# LED_Array.net
KiCad netlist of a schematic drawn in Altium Designer
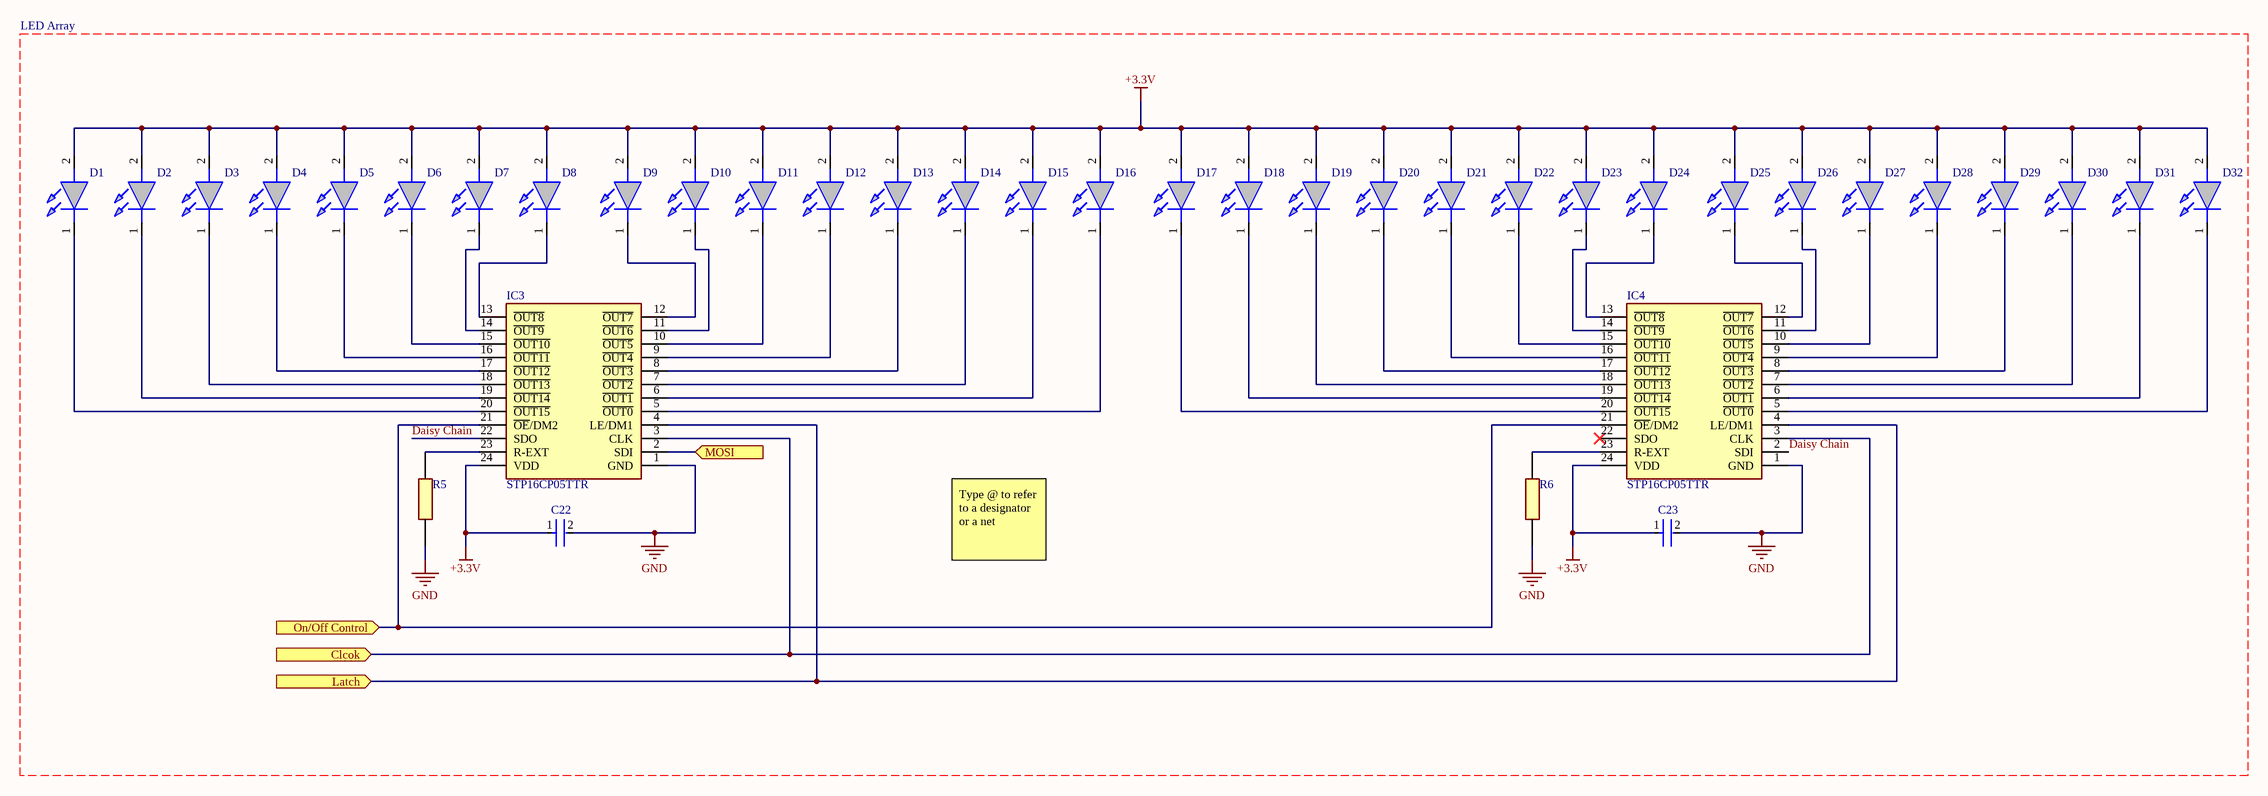
[diagram p0: LED_Array.SchDoc]

(export (version "E")
  (design (tool "Eeschema 10.0.6"))
  (components
    (comp (ref "C22")
      (value "CL31B104KBP5PNF")
      (footprint "FP-CL31-IPC_C")
      (description "Cap Ceramic 100nF 50V X7R ±10% SMD 1206 +125°C Embossed T/R")
      (fields (field (name "TOLERANCE") "10%"))
      (libsource (lib "Altium Content Vault") (part "b4654b650e69147ec39a6b967a45e02"))
    )
    (comp (ref "C23")
      (value "CL31B104KBP5PNF")
      (footprint "FP-CL31-IPC_C")
      (description "Cap Ceramic 100nF 50V X7R ±10% SMD 1206 +125°C Embossed T/R")
      (fields (field (name "TOLERANCE") "10%"))
      (libsource (lib "Altium Content Vault") (part "b4654b650e69147ec39a6b967a45e02"))
    )
    (comp (ref "D1")
      (value "LR_T64F-BBDB-1-1")
      (footprint "LEDM3528X380N")
      (description "Standard LEDs - SMD Red")
      (fields
        (field (name "MOUSER PART NUMBER") "720-LRT64FBBDB11")
        (field (name "MANUFACTURER_PART_NUMBER") "LR T64F-BBDB-1-1")
      )
      (libsource (lib "LR_T64F-BBDB-1-1") (part "LR_T64F-BBDB-1-1"))
    )
    (comp (ref "D2")
      (value "LR_T64F-BBDB-1-1")
      (footprint "LEDM3528X380N")
      (description "Standard LEDs - SMD Red")
      (fields
        (field (name "MOUSER PART NUMBER") "720-LRT64FBBDB11")
        (field (name "MANUFACTURER_PART_NUMBER") "LR T64F-BBDB-1-1")
      )
      (libsource (lib "LR_T64F-BBDB-1-1") (part "LR_T64F-BBDB-1-1"))
    )
    (comp (ref "D3")
      (value "LR_T64F-BBDB-1-1")
      (footprint "LEDM3528X380N")
      (description "Standard LEDs - SMD Red")
      (fields
        (field (name "MOUSER PART NUMBER") "720-LRT64FBBDB11")
        (field (name "MANUFACTURER_PART_NUMBER") "LR T64F-BBDB-1-1")
      )
      (libsource (lib "LR_T64F-BBDB-1-1") (part "LR_T64F-BBDB-1-1"))
    )
    (comp (ref "D4")
      (value "LR_T64F-BBDB-1-1")
      (footprint "LEDM3528X380N")
      (description "Standard LEDs - SMD Red")
      (fields
        (field (name "MOUSER PART NUMBER") "720-LRT64FBBDB11")
        (field (name "MANUFACTURER_PART_NUMBER") "LR T64F-BBDB-1-1")
      )
      (libsource (lib "LR_T64F-BBDB-1-1") (part "LR_T64F-BBDB-1-1"))
    )
    (comp (ref "D5")
      (value "LR_T64F-BBDB-1-1")
      (footprint "LEDM3528X380N")
      (description "Standard LEDs - SMD Red")
      (fields
        (field (name "MOUSER PART NUMBER") "720-LRT64FBBDB11")
        (field (name "MANUFACTURER_PART_NUMBER") "LR T64F-BBDB-1-1")
      )
      (libsource (lib "LR_T64F-BBDB-1-1") (part "LR_T64F-BBDB-1-1"))
    )
    (comp (ref "D6")
      (value "LR_T64F-BBDB-1-1")
      (footprint "LEDM3528X380N")
      (description "Standard LEDs - SMD Red")
      (fields
        (field (name "MOUSER PART NUMBER") "720-LRT64FBBDB11")
        (field (name "MANUFACTURER_PART_NUMBER") "LR T64F-BBDB-1-1")
      )
      (libsource (lib "LR_T64F-BBDB-1-1") (part "LR_T64F-BBDB-1-1"))
    )
    (comp (ref "D7")
      (value "LR_T64F-BBDB-1-1")
      (footprint "LEDM3528X380N")
      (description "Standard LEDs - SMD Red")
      (fields
        (field (name "MOUSER PART NUMBER") "720-LRT64FBBDB11")
        (field (name "MANUFACTURER_PART_NUMBER") "LR T64F-BBDB-1-1")
      )
      (libsource (lib "LR_T64F-BBDB-1-1") (part "LR_T64F-BBDB-1-1"))
    )
    (comp (ref "D8")
      (value "LR_T64F-BBDB-1-1")
      (footprint "LEDM3528X380N")
      (description "Standard LEDs - SMD Red")
      (fields
        (field (name "MOUSER PART NUMBER") "720-LRT64FBBDB11")
        (field (name "MANUFACTURER_PART_NUMBER") "LR T64F-BBDB-1-1")
      )
      (libsource (lib "LR_T64F-BBDB-1-1") (part "LR_T64F-BBDB-1-1"))
    )
    (comp (ref "D9")
      (value "LR_T64F-BBDB-1-1")
      (footprint "LEDM3528X380N")
      (description "Standard LEDs - SMD Red")
      (fields
        (field (name "MOUSER PART NUMBER") "720-LRT64FBBDB11")
        (field (name "MANUFACTURER_PART_NUMBER") "LR T64F-BBDB-1-1")
      )
      (libsource (lib "LR_T64F-BBDB-1-1") (part "LR_T64F-BBDB-1-1"))
    )
    (comp (ref "D10")
      (value "LR_T64F-BBDB-1-1")
      (footprint "LEDM3528X380N")
      (description "Standard LEDs - SMD Red")
      (fields
        (field (name "MOUSER PART NUMBER") "720-LRT64FBBDB11")
        (field (name "MANUFACTURER_PART_NUMBER") "LR T64F-BBDB-1-1")
      )
      (libsource (lib "LR_T64F-BBDB-1-1") (part "LR_T64F-BBDB-1-1"))
    )
    (comp (ref "D11")
      (value "LR_T64F-BBDB-1-1")
      (footprint "LEDM3528X380N")
      (description "Standard LEDs - SMD Red")
      (fields
        (field (name "MOUSER PART NUMBER") "720-LRT64FBBDB11")
        (field (name "MANUFACTURER_PART_NUMBER") "LR T64F-BBDB-1-1")
      )
      (libsource (lib "LR_T64F-BBDB-1-1") (part "LR_T64F-BBDB-1-1"))
    )
    (comp (ref "D12")
      (value "LR_T64F-BBDB-1-1")
      (footprint "LEDM3528X380N")
      (description "Standard LEDs - SMD Red")
      (fields
        (field (name "MOUSER PART NUMBER") "720-LRT64FBBDB11")
        (field (name "MANUFACTURER_PART_NUMBER") "LR T64F-BBDB-1-1")
      )
      (libsource (lib "LR_T64F-BBDB-1-1") (part "LR_T64F-BBDB-1-1"))
    )
    (comp (ref "D13")
      (value "LR_T64F-BBDB-1-1")
      (footprint "LEDM3528X380N")
      (description "Standard LEDs - SMD Red")
      (fields
        (field (name "MOUSER PART NUMBER") "720-LRT64FBBDB11")
        (field (name "MANUFACTURER_PART_NUMBER") "LR T64F-BBDB-1-1")
      )
      (libsource (lib "LR_T64F-BBDB-1-1") (part "LR_T64F-BBDB-1-1"))
    )
    (comp (ref "D14")
      (value "LR_T64F-BBDB-1-1")
      (footprint "LEDM3528X380N")
      (description "Standard LEDs - SMD Red")
      (fields
        (field (name "MOUSER PART NUMBER") "720-LRT64FBBDB11")
        (field (name "MANUFACTURER_PART_NUMBER") "LR T64F-BBDB-1-1")
      )
      (libsource (lib "LR_T64F-BBDB-1-1") (part "LR_T64F-BBDB-1-1"))
    )
    (comp (ref "D15")
      (value "LR_T64F-BBDB-1-1")
      (footprint "LEDM3528X380N")
      (description "Standard LEDs - SMD Red")
      (fields
        (field (name "MOUSER PART NUMBER") "720-LRT64FBBDB11")
        (field (name "MANUFACTURER_PART_NUMBER") "LR T64F-BBDB-1-1")
      )
      (libsource (lib "LR_T64F-BBDB-1-1") (part "LR_T64F-BBDB-1-1"))
    )
    (comp (ref "D16")
      (value "LR_T64F-BBDB-1-1")
      (footprint "LEDM3528X380N")
      (description "Standard LEDs - SMD Red")
      (fields
        (field (name "MOUSER PART NUMBER") "720-LRT64FBBDB11")
        (field (name "MANUFACTURER_PART_NUMBER") "LR T64F-BBDB-1-1")
      )
      (libsource (lib "LR_T64F-BBDB-1-1") (part "LR_T64F-BBDB-1-1"))
    )
    (comp (ref "D17")
      (value "LR_T64F-BBDB-1-1")
      (footprint "LEDM3528X380N")
      (description "Standard LEDs - SMD Red")
      (fields
        (field (name "MOUSER PART NUMBER") "720-LRT64FBBDB11")
        (field (name "MANUFACTURER_PART_NUMBER") "LR T64F-BBDB-1-1")
      )
      (libsource (lib "LR_T64F-BBDB-1-1") (part "LR_T64F-BBDB-1-1"))
    )
    (comp (ref "D18")
      (value "LR_T64F-BBDB-1-1")
      (footprint "LEDM3528X380N")
      (description "Standard LEDs - SMD Red")
      (fields
        (field (name "MOUSER PART NUMBER") "720-LRT64FBBDB11")
        (field (name "MANUFACTURER_PART_NUMBER") "LR T64F-BBDB-1-1")
      )
      (libsource (lib "LR_T64F-BBDB-1-1") (part "LR_T64F-BBDB-1-1"))
    )
    (comp (ref "D19")
      (value "LR_T64F-BBDB-1-1")
      (footprint "LEDM3528X380N")
      (description "Standard LEDs - SMD Red")
      (fields
        (field (name "MOUSER PART NUMBER") "720-LRT64FBBDB11")
        (field (name "MANUFACTURER_PART_NUMBER") "LR T64F-BBDB-1-1")
      )
      (libsource (lib "LR_T64F-BBDB-1-1") (part "LR_T64F-BBDB-1-1"))
    )
    (comp (ref "D20")
      (value "LR_T64F-BBDB-1-1")
      (footprint "LEDM3528X380N")
      (description "Standard LEDs - SMD Red")
      (fields
        (field (name "MOUSER PART NUMBER") "720-LRT64FBBDB11")
        (field (name "MANUFACTURER_PART_NUMBER") "LR T64F-BBDB-1-1")
      )
      (libsource (lib "LR_T64F-BBDB-1-1") (part "LR_T64F-BBDB-1-1"))
    )
    (comp (ref "D21")
      (value "LR_T64F-BBDB-1-1")
      (footprint "LEDM3528X380N")
      (description "Standard LEDs - SMD Red")
      (fields
        (field (name "MOUSER PART NUMBER") "720-LRT64FBBDB11")
        (field (name "MANUFACTURER_PART_NUMBER") "LR T64F-BBDB-1-1")
      )
      (libsource (lib "LR_T64F-BBDB-1-1") (part "LR_T64F-BBDB-1-1"))
    )
    (comp (ref "D22")
      (value "LR_T64F-BBDB-1-1")
      (footprint "LEDM3528X380N")
      (description "Standard LEDs - SMD Red")
      (fields
        (field (name "MOUSER PART NUMBER") "720-LRT64FBBDB11")
        (field (name "MANUFACTURER_PART_NUMBER") "LR T64F-BBDB-1-1")
      )
      (libsource (lib "LR_T64F-BBDB-1-1") (part "LR_T64F-BBDB-1-1"))
    )
    (comp (ref "D23")
      (value "LR_T64F-BBDB-1-1")
      (footprint "LEDM3528X380N")
      (description "Standard LEDs - SMD Red")
      (fields
        (field (name "MOUSER PART NUMBER") "720-LRT64FBBDB11")
        (field (name "MANUFACTURER_PART_NUMBER") "LR T64F-BBDB-1-1")
      )
      (libsource (lib "LR_T64F-BBDB-1-1") (part "LR_T64F-BBDB-1-1"))
    )
    (comp (ref "D24")
      (value "LR_T64F-BBDB-1-1")
      (footprint "LEDM3528X380N")
      (description "Standard LEDs - SMD Red")
      (fields
        (field (name "MOUSER PART NUMBER") "720-LRT64FBBDB11")
        (field (name "MANUFACTURER_PART_NUMBER") "LR T64F-BBDB-1-1")
      )
      (libsource (lib "LR_T64F-BBDB-1-1") (part "LR_T64F-BBDB-1-1"))
    )
    (comp (ref "D25")
      (value "LR_T64F-BBDB-1-1")
      (footprint "LEDM3528X380N")
      (description "Standard LEDs - SMD Red")
      (fields
        (field (name "MOUSER PART NUMBER") "720-LRT64FBBDB11")
        (field (name "MANUFACTURER_PART_NUMBER") "LR T64F-BBDB-1-1")
      )
      (libsource (lib "LR_T64F-BBDB-1-1") (part "LR_T64F-BBDB-1-1"))
    )
    (comp (ref "D26")
      (value "LR_T64F-BBDB-1-1")
      (footprint "LEDM3528X380N")
      (description "Standard LEDs - SMD Red")
      (fields
        (field (name "MOUSER PART NUMBER") "720-LRT64FBBDB11")
        (field (name "MANUFACTURER_PART_NUMBER") "LR T64F-BBDB-1-1")
      )
      (libsource (lib "LR_T64F-BBDB-1-1") (part "LR_T64F-BBDB-1-1"))
    )
    (comp (ref "D27")
      (value "LR_T64F-BBDB-1-1")
      (footprint "LEDM3528X380N")
      (description "Standard LEDs - SMD Red")
      (fields
        (field (name "MOUSER PART NUMBER") "720-LRT64FBBDB11")
        (field (name "MANUFACTURER_PART_NUMBER") "LR T64F-BBDB-1-1")
      )
      (libsource (lib "LR_T64F-BBDB-1-1") (part "LR_T64F-BBDB-1-1"))
    )
    (comp (ref "D28")
      (value "LR_T64F-BBDB-1-1")
      (footprint "LEDM3528X380N")
      (description "Standard LEDs - SMD Red")
      (fields
        (field (name "MOUSER PART NUMBER") "720-LRT64FBBDB11")
        (field (name "MANUFACTURER_PART_NUMBER") "LR T64F-BBDB-1-1")
      )
      (libsource (lib "LR_T64F-BBDB-1-1") (part "LR_T64F-BBDB-1-1"))
    )
    (comp (ref "D29")
      (value "LR_T64F-BBDB-1-1")
      (footprint "LEDM3528X380N")
      (description "Standard LEDs - SMD Red")
      (fields
        (field (name "MOUSER PART NUMBER") "720-LRT64FBBDB11")
        (field (name "MANUFACTURER_PART_NUMBER") "LR T64F-BBDB-1-1")
      )
      (libsource (lib "LR_T64F-BBDB-1-1") (part "LR_T64F-BBDB-1-1"))
    )
    (comp (ref "D30")
      (value "LR_T64F-BBDB-1-1")
      (footprint "LEDM3528X380N")
      (description "Standard LEDs - SMD Red")
      (fields
        (field (name "MOUSER PART NUMBER") "720-LRT64FBBDB11")
        (field (name "MANUFACTURER_PART_NUMBER") "LR T64F-BBDB-1-1")
      )
      (libsource (lib "LR_T64F-BBDB-1-1") (part "LR_T64F-BBDB-1-1"))
    )
    (comp (ref "D31")
      (value "LR_T64F-BBDB-1-1")
      (footprint "LEDM3528X380N")
      (description "Standard LEDs - SMD Red")
      (fields
        (field (name "MOUSER PART NUMBER") "720-LRT64FBBDB11")
        (field (name "MANUFACTURER_PART_NUMBER") "LR T64F-BBDB-1-1")
      )
      (libsource (lib "LR_T64F-BBDB-1-1") (part "LR_T64F-BBDB-1-1"))
    )
    (comp (ref "D32")
      (value "LR_T64F-BBDB-1-1")
      (footprint "LEDM3528X380N")
      (description "Standard LEDs - SMD Red")
      (fields
        (field (name "MOUSER PART NUMBER") "720-LRT64FBBDB11")
        (field (name "MANUFACTURER_PART_NUMBER") "LR T64F-BBDB-1-1")
      )
      (libsource (lib "LR_T64F-BBDB-1-1") (part "LR_T64F-BBDB-1-1"))
    )
    (comp (ref "IC3")
      (value "STP16CP05TTR")
      (footprint "SOP65P638X110-24N")
      (description "STMICROELECTRONICS - STP16CP05TTR - IC LED SINK DRIVER, 16-BIT, LO V")
      (fields (field (name "MOUSER PART NUMBER") "511-STP16CP05TTR"))
      (libsource (lib "STP16CP05TTR") (part "STP16CP05TTR"))
    )
    (comp (ref "IC4")
      (value "STP16CP05TTR")
      (footprint "SOP65P638X110-24N")
      (description "STMICROELECTRONICS - STP16CP05TTR - IC LED SINK DRIVER, 16-BIT, LO V")
      (fields (field (name "MOUSER PART NUMBER") "511-STP16CP05TTR"))
      (libsource (lib "STP16CP05TTR") (part "STP16CP05TTR"))
    )
    (comp (ref "R5")
      (value "ERA-8APB122V")
      (footprint "RESC3216X70N")
      (description "Thin Film Resistors - SMD 1206 Thin film chip resistor")
      (fields (field (name "MOUSER PART NUMBER") "667-ERA-8APB122V"))
      (libsource (lib "ERA-8APB122V") (part "ERA-8APB122V"))
    )
    (comp (ref "R6")
      (value "ERA-8APB122V")
      (footprint "RESC3216X70N")
      (description "Thin Film Resistors - SMD 1206 Thin film chip resistor")
      (fields (field (name "MOUSER PART NUMBER") "667-ERA-8APB122V"))
      (libsource (lib "ERA-8APB122V") (part "ERA-8APB122V"))
    )
  )
  (nets
    (net (code "1") (name "+3.3V") (class "Default")
      (node (ref "C22") (pin "1") (pinfunction "1_1") (pintype "passive"))
      (node (ref "C23") (pin "1") (pinfunction "1_1") (pintype "passive"))
      (node (ref "D1") (pin "2") (pinfunction "A_2") (pintype "passive"))
      (node (ref "D10") (pin "2") (pinfunction "A_2") (pintype "passive"))
      (node (ref "D11") (pin "2") (pinfunction "A_2") (pintype "passive"))
      (node (ref "D12") (pin "2") (pinfunction "A_2") (pintype "passive"))
      (node (ref "D13") (pin "2") (pinfunction "A_2") (pintype "passive"))
      (node (ref "D14") (pin "2") (pinfunction "A_2") (pintype "passive"))
      (node (ref "D15") (pin "2") (pinfunction "A_2") (pintype "passive"))
      (node (ref "D16") (pin "2") (pinfunction "A_2") (pintype "passive"))
      (node (ref "D17") (pin "2") (pinfunction "A_2") (pintype "passive"))
      (node (ref "D18") (pin "2") (pinfunction "A_2") (pintype "passive"))
      (node (ref "D19") (pin "2") (pinfunction "A_2") (pintype "passive"))
      (node (ref "D2") (pin "2") (pinfunction "A_2") (pintype "passive"))
      (node (ref "D20") (pin "2") (pinfunction "A_2") (pintype "passive"))
      (node (ref "D21") (pin "2") (pinfunction "A_2") (pintype "passive"))
      (node (ref "D22") (pin "2") (pinfunction "A_2") (pintype "passive"))
      (node (ref "D23") (pin "2") (pinfunction "A_2") (pintype "passive"))
      (node (ref "D24") (pin "2") (pinfunction "A_2") (pintype "passive"))
      (node (ref "D25") (pin "2") (pinfunction "A_2") (pintype "passive"))
      (node (ref "D26") (pin "2") (pinfunction "A_2") (pintype "passive"))
      (node (ref "D27") (pin "2") (pinfunction "A_2") (pintype "passive"))
      (node (ref "D28") (pin "2") (pinfunction "A_2") (pintype "passive"))
      (node (ref "D29") (pin "2") (pinfunction "A_2") (pintype "passive"))
      (node (ref "D3") (pin "2") (pinfunction "A_2") (pintype "passive"))
      (node (ref "D30") (pin "2") (pinfunction "A_2") (pintype "passive"))
      (node (ref "D31") (pin "2") (pinfunction "A_2") (pintype "passive"))
      (node (ref "D32") (pin "2") (pinfunction "A_2") (pintype "passive"))
      (node (ref "D4") (pin "2") (pinfunction "A_2") (pintype "passive"))
      (node (ref "D5") (pin "2") (pinfunction "A_2") (pintype "passive"))
      (node (ref "D6") (pin "2") (pinfunction "A_2") (pintype "passive"))
      (node (ref "D7") (pin "2") (pinfunction "A_2") (pintype "passive"))
      (node (ref "D8") (pin "2") (pinfunction "A_2") (pintype "passive"))
      (node (ref "D9") (pin "2") (pinfunction "A_2") (pintype "passive"))
      (node (ref "IC3") (pin "24") (pinfunction "VDD_24") (pintype "passive"))
      (node (ref "IC4") (pin "24") (pinfunction "VDD_24") (pintype "passive"))
    )
    (net (code "2") (name "/Clcok") (class "Default")
      (node (ref "IC3") (pin "3") (pinfunction "CLK_3") (pintype "passive"))
      (node (ref "IC4") (pin "3") (pinfunction "CLK_3") (pintype "passive"))
    )
    (net (code "3") (name "/Daisy Chain") (class "Default")
      (node (ref "IC3") (pin "22") (pinfunction "SDO_22") (pintype "passive"))
      (node (ref "IC4") (pin "2") (pinfunction "SDI_2") (pintype "passive"))
    )
    (net (code "4") (name "/Latch") (class "Default")
      (node (ref "IC3") (pin "4") (pinfunction "LE/DM1_4") (pintype "passive"))
      (node (ref "IC4") (pin "4") (pinfunction "LE/DM1_4") (pintype "passive"))
    )
    (net (code "5") (name "/MOSI") (class "Default")
      (node (ref "IC3") (pin "2") (pinfunction "SDI_2") (pintype "passive"))
    )
    (net (code "6") (name "/On{slash}Off Control") (class "Default")
      (node (ref "IC3") (pin "21") (pinfunction "~{OE}/DM2_21") (pintype "passive"))
      (node (ref "IC4") (pin "21") (pinfunction "~{OE}/DM2_21") (pintype "passive"))
    )
    (net (code "7") (name "GND") (class "Default")
      (node (ref "C22") (pin "2") (pinfunction "2_2") (pintype "passive"))
      (node (ref "C23") (pin "2") (pinfunction "2_2") (pintype "passive"))
      (node (ref "IC3") (pin "1") (pinfunction "GND_1") (pintype "passive"))
      (node (ref "IC4") (pin "1") (pinfunction "GND_1") (pintype "passive"))
      (node (ref "R5") (pin "1") (pinfunction "1_1") (pintype "passive"))
      (node (ref "R6") (pin "1") (pinfunction "1_1") (pintype "passive"))
    )
    (net (code "8") (name "Net-(D1-K)") (class "Default")
      (node (ref "D1") (pin "1") (pinfunction "K_1") (pintype "passive"))
      (node (ref "IC3") (pin "20") (pinfunction "~{OUT15}_20") (pintype "passive"))
    )
    (net (code "9") (name "Net-(D2-K)") (class "Default")
      (node (ref "D2") (pin "1") (pinfunction "K_1") (pintype "passive"))
      (node (ref "IC3") (pin "19") (pinfunction "~{OUT14}_19") (pintype "passive"))
    )
    (net (code "10") (name "Net-(D3-K)") (class "Default")
      (node (ref "D3") (pin "1") (pinfunction "K_1") (pintype "passive"))
      (node (ref "IC3") (pin "18") (pinfunction "~{OUT13}_18") (pintype "passive"))
    )
    (net (code "11") (name "Net-(D4-K)") (class "Default")
      (node (ref "D4") (pin "1") (pinfunction "K_1") (pintype "passive"))
      (node (ref "IC3") (pin "17") (pinfunction "~{OUT12}_17") (pintype "passive"))
    )
    (net (code "12") (name "Net-(D5-K)") (class "Default")
      (node (ref "D5") (pin "1") (pinfunction "K_1") (pintype "passive"))
      (node (ref "IC3") (pin "16") (pinfunction "~{OUT11}_16") (pintype "passive"))
    )
    (net (code "13") (name "Net-(D6-K)") (class "Default")
      (node (ref "D6") (pin "1") (pinfunction "K_1") (pintype "passive"))
      (node (ref "IC3") (pin "15") (pinfunction "~{OUT10}_15") (pintype "passive"))
    )
    (net (code "14") (name "Net-(D7-K)") (class "Default")
      (node (ref "D7") (pin "1") (pinfunction "K_1") (pintype "passive"))
      (node (ref "IC3") (pin "14") (pinfunction "~{OUT9}_14") (pintype "passive"))
    )
    (net (code "15") (name "Net-(D8-K)") (class "Default")
      (node (ref "D8") (pin "1") (pinfunction "K_1") (pintype "passive"))
      (node (ref "IC3") (pin "13") (pinfunction "~{OUT8}_13") (pintype "passive"))
    )
    (net (code "16") (name "Net-(D9-K)") (class "Default")
      (node (ref "D9") (pin "1") (pinfunction "K_1") (pintype "passive"))
      (node (ref "IC3") (pin "12") (pinfunction "~{OUT7}_12") (pintype "passive"))
    )
    (net (code "17") (name "Net-(D10-K)") (class "Default")
      (node (ref "D10") (pin "1") (pinfunction "K_1") (pintype "passive"))
      (node (ref "IC3") (pin "11") (pinfunction "~{OUT6}_11") (pintype "passive"))
    )
    (net (code "18") (name "Net-(D11-K)") (class "Default")
      (node (ref "D11") (pin "1") (pinfunction "K_1") (pintype "passive"))
      (node (ref "IC3") (pin "10") (pinfunction "~{OUT5}_10") (pintype "passive"))
    )
    (net (code "19") (name "Net-(D12-K)") (class "Default")
      (node (ref "D12") (pin "1") (pinfunction "K_1") (pintype "passive"))
      (node (ref "IC3") (pin "9") (pinfunction "~{OUT4}_9") (pintype "passive"))
    )
    (net (code "20") (name "Net-(D13-K)") (class "Default")
      (node (ref "D13") (pin "1") (pinfunction "K_1") (pintype "passive"))
      (node (ref "IC3") (pin "8") (pinfunction "~{OUT3}_8") (pintype "passive"))
    )
    (net (code "21") (name "Net-(D14-K)") (class "Default")
      (node (ref "D14") (pin "1") (pinfunction "K_1") (pintype "passive"))
      (node (ref "IC3") (pin "7") (pinfunction "~{OUT2}_7") (pintype "passive"))
    )
    (net (code "22") (name "Net-(D15-K)") (class "Default")
      (node (ref "D15") (pin "1") (pinfunction "K_1") (pintype "passive"))
      (node (ref "IC3") (pin "6") (pinfunction "~{OUT1}_6") (pintype "passive"))
    )
    (net (code "23") (name "Net-(D16-K)") (class "Default")
      (node (ref "D16") (pin "1") (pinfunction "K_1") (pintype "passive"))
      (node (ref "IC3") (pin "5") (pinfunction "~{OUT0}_5") (pintype "passive"))
    )
    (net (code "24") (name "Net-(D17-K)") (class "Default")
      (node (ref "D17") (pin "1") (pinfunction "K_1") (pintype "passive"))
      (node (ref "IC4") (pin "20") (pinfunction "~{OUT15}_20") (pintype "passive"))
    )
    (net (code "25") (name "Net-(D18-K)") (class "Default")
      (node (ref "D18") (pin "1") (pinfunction "K_1") (pintype "passive"))
      (node (ref "IC4") (pin "19") (pinfunction "~{OUT14}_19") (pintype "passive"))
    )
    (net (code "26") (name "Net-(D19-K)") (class "Default")
      (node (ref "D19") (pin "1") (pinfunction "K_1") (pintype "passive"))
      (node (ref "IC4") (pin "18") (pinfunction "~{OUT13}_18") (pintype "passive"))
    )
    (net (code "27") (name "Net-(D20-K)") (class "Default")
      (node (ref "D20") (pin "1") (pinfunction "K_1") (pintype "passive"))
      (node (ref "IC4") (pin "17") (pinfunction "~{OUT12}_17") (pintype "passive"))
    )
    (net (code "28") (name "Net-(D21-K)") (class "Default")
      (node (ref "D21") (pin "1") (pinfunction "K_1") (pintype "passive"))
      (node (ref "IC4") (pin "16") (pinfunction "~{OUT11}_16") (pintype "passive"))
    )
    (net (code "29") (name "Net-(D22-K)") (class "Default")
      (node (ref "D22") (pin "1") (pinfunction "K_1") (pintype "passive"))
      (node (ref "IC4") (pin "15") (pinfunction "~{OUT10}_15") (pintype "passive"))
    )
    (net (code "30") (name "Net-(D23-K)") (class "Default")
      (node (ref "D23") (pin "1") (pinfunction "K_1") (pintype "passive"))
      (node (ref "IC4") (pin "14") (pinfunction "~{OUT9}_14") (pintype "passive"))
    )
    (net (code "31") (name "Net-(D24-K)") (class "Default")
      (node (ref "D24") (pin "1") (pinfunction "K_1") (pintype "passive"))
      (node (ref "IC4") (pin "13") (pinfunction "~{OUT8}_13") (pintype "passive"))
    )
    (net (code "32") (name "Net-(D25-K)") (class "Default")
      (node (ref "D25") (pin "1") (pinfunction "K_1") (pintype "passive"))
      (node (ref "IC4") (pin "12") (pinfunction "~{OUT7}_12") (pintype "passive"))
    )
    (net (code "33") (name "Net-(D26-K)") (class "Default")
      (node (ref "D26") (pin "1") (pinfunction "K_1") (pintype "passive"))
      (node (ref "IC4") (pin "11") (pinfunction "~{OUT6}_11") (pintype "passive"))
    )
    (net (code "34") (name "Net-(D27-K)") (class "Default")
      (node (ref "D27") (pin "1") (pinfunction "K_1") (pintype "passive"))
      (node (ref "IC4") (pin "10") (pinfunction "~{OUT5}_10") (pintype "passive"))
    )
    (net (code "35") (name "Net-(D28-K)") (class "Default")
      (node (ref "D28") (pin "1") (pinfunction "K_1") (pintype "passive"))
      (node (ref "IC4") (pin "9") (pinfunction "~{OUT4}_9") (pintype "passive"))
    )
    (net (code "36") (name "Net-(D29-K)") (class "Default")
      (node (ref "D29") (pin "1") (pinfunction "K_1") (pintype "passive"))
      (node (ref "IC4") (pin "8") (pinfunction "~{OUT3}_8") (pintype "passive"))
    )
    (net (code "37") (name "Net-(D30-K)") (class "Default")
      (node (ref "D30") (pin "1") (pinfunction "K_1") (pintype "passive"))
      (node (ref "IC4") (pin "7") (pinfunction "~{OUT2}_7") (pintype "passive"))
    )
    (net (code "38") (name "Net-(D31-K)") (class "Default")
      (node (ref "D31") (pin "1") (pinfunction "K_1") (pintype "passive"))
      (node (ref "IC4") (pin "6") (pinfunction "~{OUT1}_6") (pintype "passive"))
    )
    (net (code "39") (name "Net-(D32-K)") (class "Default")
      (node (ref "D32") (pin "1") (pinfunction "K_1") (pintype "passive"))
      (node (ref "IC4") (pin "5") (pinfunction "~{OUT0}_5") (pintype "passive"))
    )
    (net (code "40") (name "Net-(IC3-R-EXT)") (class "Default")
      (node (ref "IC3") (pin "23") (pinfunction "R-EXT_23") (pintype "passive"))
      (node (ref "R5") (pin "2") (pinfunction "2_2") (pintype "passive"))
    )
    (net (code "41") (name "Net-(IC4-R-EXT)") (class "Default")
      (node (ref "IC4") (pin "23") (pinfunction "R-EXT_23") (pintype "passive"))
      (node (ref "R6") (pin "2") (pinfunction "2_2") (pintype "passive"))
    )
    (net (code "42") (name "unconnected-(IC4-SDO-Pad22)") (class "Default")
      (node (ref "IC4") (pin "22") (pinfunction "SDO_22") (pintype "passive+no_connect"))
    )
  )
)
